# aw_301_runner.net
KiCad netlist of a schematic drawn in EAGLE
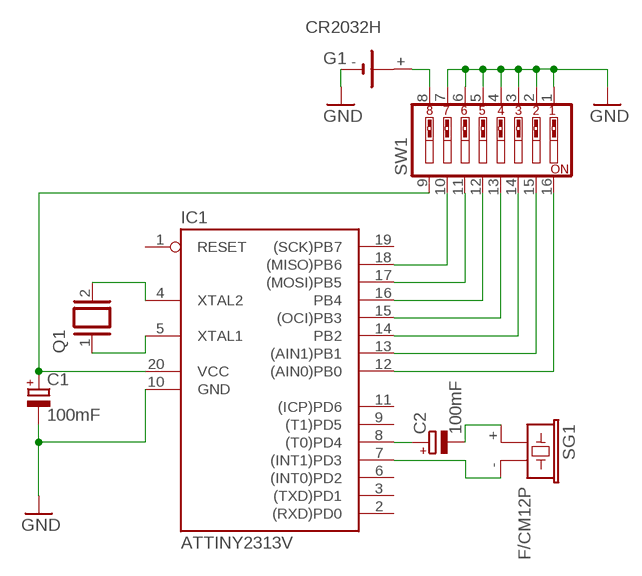
[diagram p0: schematic, sheet 1]

(export (version "E")
  (design (tool "Eeschema 10.0.6"))
  (components
    (comp (ref "C1")
      (value "100mF")
      (footprint "eagle-import:E2,5-6")
      (libsource (lib "eagle-import") (part "CPOL-EUE2.5-6"))
    )
    (comp (ref "C2")
      (value "100mF")
      (footprint "eagle-import:E2,5-6")
      (libsource (lib "eagle-import") (part "CPOL-EUE2.5-6"))
    )
    (comp (ref "G1")
      (value "CR2032H")
      (footprint "eagle-import:CR2032H")
      (libsource (lib "eagle-import") (part "CR2032H"))
    )
    (comp (ref "IC1")
      (value "ATTINY2313V")
      (footprint "eagle-import:DIL20")
      (libsource (lib "eagle-import") (part "AT90S2313P"))
    )
    (comp (ref "Q1")
      (value "XTAL")
      (footprint "eagle-import:Q")
      (libsource (lib "eagle-import") (part "XTAL"))
    )
    (comp (ref "SG1")
      (value "F/CM12P")
      (footprint "eagle-import:F_CM12P")
      (libsource (lib "eagle-import") (part "F/CM12P"))
    )
    (comp (ref "SW1")
      (value "SW_DIP-8")
      (footprint "eagle-import:EDG-08")
      (libsource (lib "eagle-import") (part "SW_DIP-8"))
    )
  )
  (nets
    (net (code "1") (name "GND") (class "Default")
      (node (ref "C1") (pin "-") (pinfunction "-_-") (pintype "passive"))
      (node (ref "G1") (pin "-") (pinfunction "-_-") (pintype "passive"))
      (node (ref "IC1") (pin "10") (pinfunction "GND_10") (pintype "power_in"))
      (node (ref "SW1") (pin "1") (pinfunction "1_1") (pintype "passive"))
      (node (ref "SW1") (pin "2") (pinfunction "2_2") (pintype "passive"))
      (node (ref "SW1") (pin "3") (pinfunction "3_3") (pintype "passive"))
      (node (ref "SW1") (pin "4") (pinfunction "4_4") (pintype "passive"))
      (node (ref "SW1") (pin "5") (pinfunction "5_5") (pintype "passive"))
      (node (ref "SW1") (pin "6") (pinfunction "6_6") (pintype "passive"))
      (node (ref "SW1") (pin "7") (pinfunction "7_7") (pintype "passive"))
    )
    (net (code "2") (name "Net-(G1-Pad+)") (class "Default")
      (node (ref "G1") (pin "+") (pinfunction "+_+") (pintype "passive"))
      (node (ref "SW1") (pin "8") (pinfunction "8_8") (pintype "passive"))
    )
    (net (code "3") (name "Net-(IC1-(AIN0)PB0)") (class "Default")
      (node (ref "IC1") (pin "12") (pinfunction "(AIN0)PB0_12") (pintype "bidirectional"))
      (node (ref "SW1") (pin "16") (pinfunction "16_16") (pintype "passive"))
    )
    (net (code "4") (name "Net-(IC1-(AIN1)PB1)") (class "Default")
      (node (ref "IC1") (pin "13") (pinfunction "(AIN1)PB1_13") (pintype "bidirectional"))
      (node (ref "SW1") (pin "15") (pinfunction "15_15") (pintype "passive"))
    )
    (net (code "5") (name "Net-(IC1-(INT1)PD3)") (class "Default")
      (node (ref "IC1") (pin "7") (pinfunction "(INT1)PD3_7") (pintype "bidirectional"))
      (node (ref "SG1") (pin "-") (pinfunction "2_-") (pintype "passive"))
    )
    (net (code "6") (name "Net-(IC1-(MISO)PB6)") (class "Default")
      (node (ref "IC1") (pin "18") (pinfunction "(MISO)PB6_18") (pintype "bidirectional"))
      (node (ref "SW1") (pin "10") (pinfunction "10_10") (pintype "passive"))
    )
    (net (code "7") (name "Net-(IC1-(MOSI)PB5)") (class "Default")
      (node (ref "IC1") (pin "17") (pinfunction "(MOSI)PB5_17") (pintype "bidirectional"))
      (node (ref "SW1") (pin "11") (pinfunction "11_11") (pintype "passive"))
    )
    (net (code "8") (name "Net-(IC1-(OCI)PB3)") (class "Default")
      (node (ref "IC1") (pin "15") (pinfunction "(OCI)PB3_15") (pintype "bidirectional"))
      (node (ref "SW1") (pin "13") (pinfunction "13_13") (pintype "passive"))
    )
    (net (code "9") (name "Net-(IC1-(T0)PD4)") (class "Default")
      (node (ref "C2") (pin "+") (pinfunction "+_+") (pintype "passive"))
      (node (ref "IC1") (pin "8") (pinfunction "(T0)PD4_8") (pintype "bidirectional"))
    )
    (net (code "10") (name "Net-(IC1-PB2)") (class "Default")
      (node (ref "IC1") (pin "14") (pinfunction "PB2_14") (pintype "bidirectional"))
      (node (ref "SW1") (pin "14") (pinfunction "14_14") (pintype "passive"))
    )
    (net (code "11") (name "Net-(IC1-PB4)") (class "Default")
      (node (ref "IC1") (pin "16") (pinfunction "PB4_16") (pintype "bidirectional"))
      (node (ref "SW1") (pin "12") (pinfunction "12_12") (pintype "passive"))
    )
    (net (code "12") (name "Net-(IC1-VCC)") (class "Default")
      (node (ref "C1") (pin "+") (pinfunction "+_+") (pintype "passive"))
      (node (ref "IC1") (pin "20") (pinfunction "VCC_20") (pintype "power_in"))
      (node (ref "SW1") (pin "9") (pinfunction "9_9") (pintype "passive"))
    )
    (net (code "13") (name "Net-(IC1-XTAL1)") (class "Default")
      (node (ref "IC1") (pin "5") (pinfunction "XTAL1_5") (pintype "bidirectional"))
      (node (ref "Q1") (pin "1") (pinfunction "1_1") (pintype "passive"))
    )
    (net (code "14") (name "Net-(IC1-XTAL2)") (class "Default")
      (node (ref "IC1") (pin "4") (pinfunction "XTAL2_4") (pintype "bidirectional"))
      (node (ref "Q1") (pin "2") (pinfunction "2_2") (pintype "passive"))
    )
    (net (code "15") (name "Net-(SG1-1)") (class "Default")
      (node (ref "C2") (pin "-") (pinfunction "-_-") (pintype "passive"))
      (node (ref "SG1") (pin "+") (pinfunction "1_+") (pintype "passive"))
    )
    (net (code "16") (name "unconnected-(G1-+-Pad+@1)") (class "Default")
      (node (ref "G1") (pin "+@1") (pinfunction "+_+@1") (pintype "passive"))
    )
    (net (code "17") (name "unconnected-(IC1-(ICP)PD6-Pad11)") (class "Default")
      (node (ref "IC1") (pin "11") (pinfunction "(ICP)PD6_11") (pintype "bidirectional"))
    )
    (net (code "18") (name "unconnected-(IC1-(INT0)PD2-Pad6)") (class "Default")
      (node (ref "IC1") (pin "6") (pinfunction "(INT0)PD2_6") (pintype "bidirectional"))
    )
    (net (code "19") (name "unconnected-(IC1-(RXD)PD0-Pad2)") (class "Default")
      (node (ref "IC1") (pin "2") (pinfunction "(RXD)PD0_2") (pintype "bidirectional"))
    )
    (net (code "20") (name "unconnected-(IC1-(SCK)PB7-Pad19)") (class "Default")
      (node (ref "IC1") (pin "19") (pinfunction "(SCK)PB7_19") (pintype "bidirectional"))
    )
    (net (code "21") (name "unconnected-(IC1-(T1)PD5-Pad9)") (class "Default")
      (node (ref "IC1") (pin "9") (pinfunction "(T1)PD5_9") (pintype "bidirectional"))
    )
    (net (code "22") (name "unconnected-(IC1-(TXD)PD1-Pad3)") (class "Default")
      (node (ref "IC1") (pin "3") (pinfunction "(TXD)PD1_3") (pintype "bidirectional"))
    )
    (net (code "23") (name "unconnected-(IC1-RESET-Pad1)") (class "Default")
      (node (ref "IC1") (pin "1") (pinfunction "RESET_1") (pintype "bidirectional"))
    )
  )
)
